# tesis_page5_adc_channels.net
KiCad netlist of a schematic drawn in Altium Designer
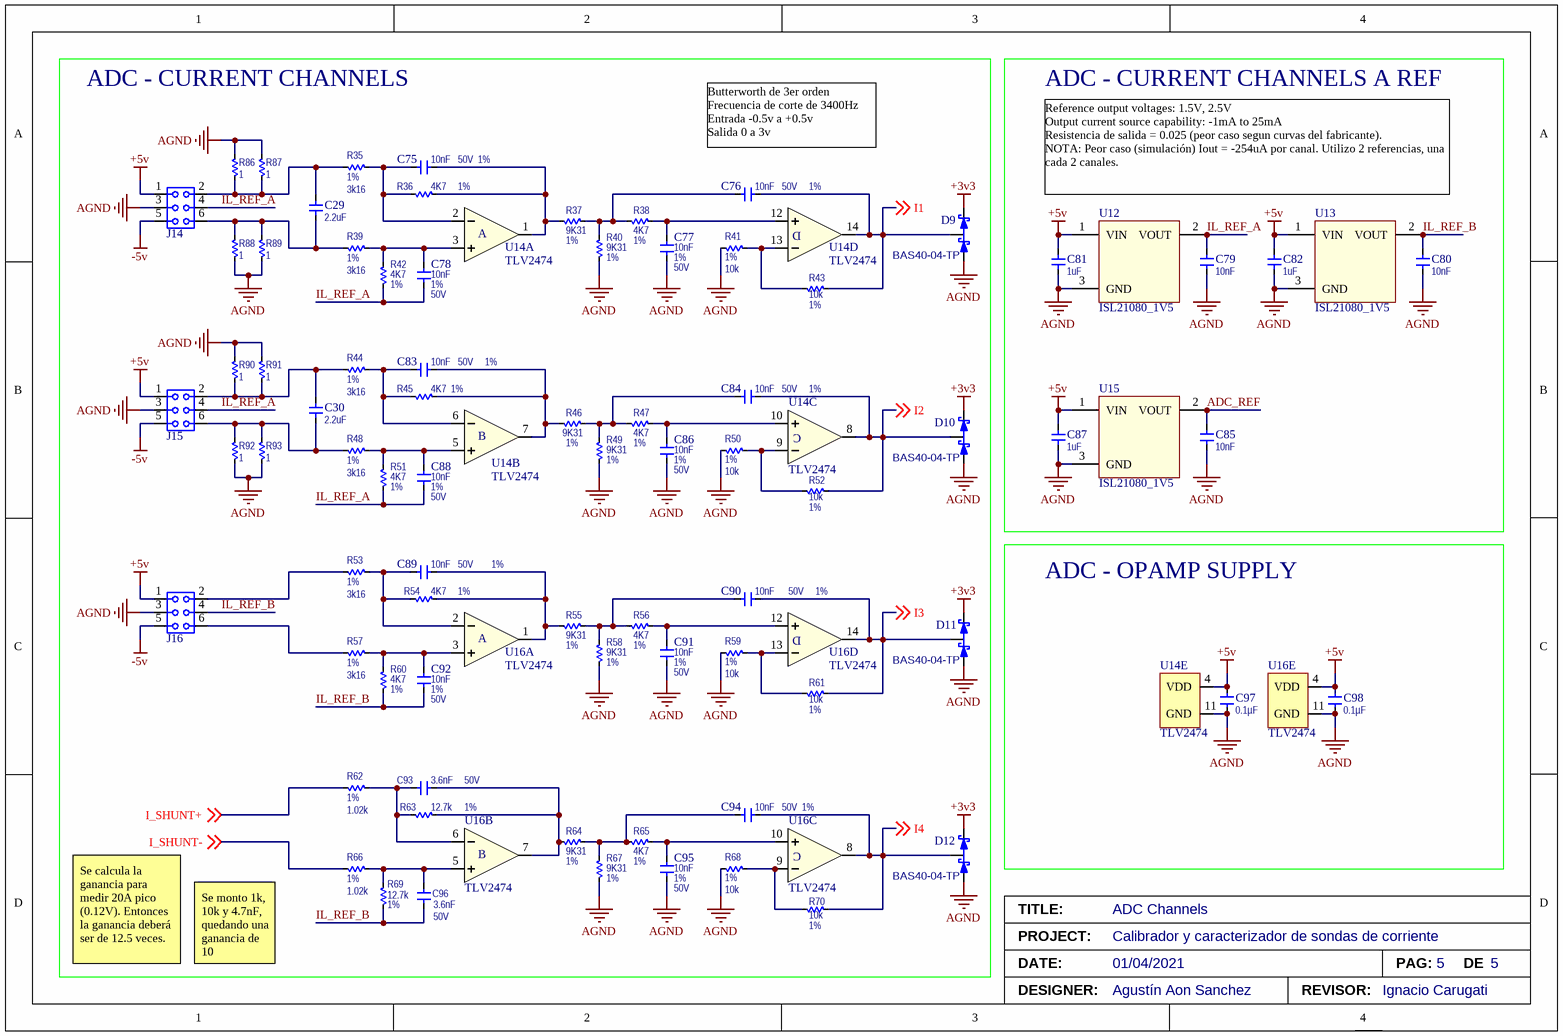
[diagram p0: tesis_page5_adc_channels.SchDoc]

(export (version "E")
  (design (tool "Eeschema 10.0.6"))
  (components
    (comp (ref "C29")
      (value "2.2uF")
      (footprint "CAPC3216X135N_B")
      (description "CAP CER 2.2UF 16V X7R 1206")
      (fields (field (name "MANUFACTURER") "YAGEO") (field (name "TOLERANCE") "10%"))
      (libsource (lib "lib_ic_CAP") (part "CAP_CC1206KKX7R7BB225_YAGEO"))
    )
    (comp (ref "C30")
      (value "2.2uF")
      (footprint "CAPC3216X135N_B")
      (description "CAP CER 2.2UF 16V X7R 1206")
      (fields (field (name "MANUFACTURER") "YAGEO") (field (name "TOLERANCE") "10%"))
      (libsource (lib "lib_ic_CAP") (part "CAP_CC1206KKX7R7BB225_YAGEO"))
    )
    (comp (ref "C75")
      (value "10nF")
      (footprint "CAPC2013X110N")
      (description "CAP CER 10000PF 50V NP0 0805")
      (fields
        (field (name "MANUFACTURER") "Murata Electronics North America")
        (field (name "TOLERANCE") "1%")
        (field (name "VOLTAGE RATING") "50V")
        (field (name "DIGIKEY PART NUMBER") "490-8295-1-ND")
      )
      (libsource (lib "pqm_v2_lib_cap") (part "CAP_GRM2195C1H103FA01D_MURATA"))
    )
    (comp (ref "C76")
      (value "10nF")
      (footprint "CAPC2013X110N")
      (description "CAP CER 10000PF 50V NP0 0805")
      (fields
        (field (name "MANUFACTURER") "Murata Electronics North America")
        (field (name "TOLERANCE") "1%")
        (field (name "VOLTAGE RATING") "50V")
        (field (name "DIGIKEY PART NUMBER") "490-8295-1-ND")
      )
      (libsource (lib "pqm_v2_lib_cap") (part "CAP_GRM2195C1H103FA01D_MURATA"))
    )
    (comp (ref "C77")
      (value "10nF")
      (footprint "CAPC2013X110N")
      (description "CAP CER 10000PF 50V NP0 0805")
      (fields
        (field (name "MANUFACTURER") "Murata Electronics North America")
        (field (name "TOLERANCE") "1%")
        (field (name "VOLTAGE RATING") "50V")
        (field (name "DIGIKEY PART NUMBER") "490-8295-1-ND")
      )
      (libsource (lib "pqm_v2_lib_cap") (part "CAP_GRM2195C1H103FA01D_MURATA"))
    )
    (comp (ref "C78")
      (value "10nF")
      (footprint "CAPC2013X110N")
      (description "CAP CER 10000PF 50V NP0 0805")
      (fields
        (field (name "MANUFACTURER") "Murata Electronics North America")
        (field (name "TOLERANCE") "1%")
        (field (name "VOLTAGE RATING") "50V")
        (field (name "DIGIKEY PART NUMBER") "490-8295-1-ND")
      )
      (libsource (lib "pqm_v2_lib_cap") (part "CAP_GRM2195C1H103FA01D_MURATA"))
    )
    (comp (ref "C79")
      (value "10nF")
      (footprint "CAPC2013X110N")
      (description "CAP CER 10000PF 50V NP0 0805")
      (fields
        (field (name "MANUFACTURER") "Murata Electronics North America")
        (field (name "DIGIKEY PART NUMBER") "490-8295-1-ND")
      )
      (libsource (lib "lib_ic_CAP") (part "CAP_GRM2195C1H103FA01D_MURATA"))
    )
    (comp (ref "C80")
      (value "10nF")
      (footprint "CAPC2013X110N")
      (description "CAP CER 10000PF 50V NP0 0805")
      (fields
        (field (name "MANUFACTURER") "Murata Electronics North America")
        (field (name "DIGIKEY PART NUMBER") "490-8295-1-ND")
      )
      (libsource (lib "lib_ic_CAP") (part "CAP_GRM2195C1H103FA01D_MURATA"))
    )
    (comp (ref "C81")
      (value "1uF")
      (footprint "CAPC2013X110N")
      (description "CAP CER 1UF 16V X7R 0805")
      (fields (field (name "MANUFACTURER") "YAGEO") (field (name "TOLERANCE") "10%"))
      (libsource (lib "pqm_v2_lib_cap") (part "CAP_CC0805KKX7R7BB105_YAGEO"))
    )
    (comp (ref "C82")
      (value "1uF")
      (footprint "CAPC2013X110N")
      (description "CAP CER 1UF 16V X7R 0805")
      (fields (field (name "MANUFACTURER") "YAGEO") (field (name "TOLERANCE") "10%"))
      (libsource (lib "pqm_v2_lib_cap") (part "CAP_CC0805KKX7R7BB105_YAGEO"))
    )
    (comp (ref "C83")
      (value "10nF")
      (footprint "CAPC2013X110N")
      (description "CAP CER 10000PF 50V NP0 0805")
      (fields
        (field (name "MANUFACTURER") "Murata Electronics North America")
        (field (name "TOLERANCE") "1%")
        (field (name "VOLTAGE RATING") "50V")
        (field (name "DIGIKEY PART NUMBER") "490-8295-1-ND")
      )
      (libsource (lib "pqm_v2_lib_cap") (part "CAP_GRM2195C1H103FA01D_MURATA"))
    )
    (comp (ref "C84")
      (value "10nF")
      (footprint "CAPC2013X110N")
      (description "CAP CER 10000PF 50V NP0 0805")
      (fields
        (field (name "MANUFACTURER") "Murata Electronics North America")
        (field (name "TOLERANCE") "1%")
        (field (name "VOLTAGE RATING") "50V")
        (field (name "DIGIKEY PART NUMBER") "490-8295-1-ND")
      )
      (libsource (lib "pqm_v2_lib_cap") (part "CAP_GRM2195C1H103FA01D_MURATA"))
    )
    (comp (ref "C85")
      (value "10nF")
      (footprint "CAPC2013X110N")
      (description "CAP CER 10000PF 50V NP0 0805")
      (fields
        (field (name "MANUFACTURER") "Murata Electronics North America")
        (field (name "DIGIKEY PART NUMBER") "490-8295-1-ND")
      )
      (libsource (lib "lib_ic_CAP") (part "CAP_GRM2195C1H103FA01D_MURATA"))
    )
    (comp (ref "C86")
      (value "10nF")
      (footprint "CAPC2013X110N")
      (description "CAP CER 10000PF 50V NP0 0805")
      (fields
        (field (name "MANUFACTURER") "Murata Electronics North America")
        (field (name "TOLERANCE") "1%")
        (field (name "VOLTAGE RATING") "50V")
        (field (name "DIGIKEY PART NUMBER") "490-8295-1-ND")
      )
      (libsource (lib "pqm_v2_lib_cap") (part "CAP_GRM2195C1H103FA01D_MURATA"))
    )
    (comp (ref "C87")
      (value "1uF")
      (footprint "CAPC2013X110N")
      (description "CAP CER 1UF 16V X7R 0805")
      (fields (field (name "MANUFACTURER") "YAGEO") (field (name "TOLERANCE") "10%"))
      (libsource (lib "pqm_v2_lib_cap") (part "CAP_CC0805KKX7R7BB105_YAGEO"))
    )
    (comp (ref "C88")
      (value "10nF")
      (footprint "CAPC2013X110N")
      (description "CAP CER 10000PF 50V NP0 0805")
      (fields
        (field (name "MANUFACTURER") "Murata Electronics North America")
        (field (name "TOLERANCE") "1%")
        (field (name "VOLTAGE RATING") "50V")
        (field (name "DIGIKEY PART NUMBER") "490-8295-1-ND")
      )
      (libsource (lib "pqm_v2_lib_cap") (part "CAP_GRM2195C1H103FA01D_MURATA"))
    )
    (comp (ref "C89")
      (value "10nF")
      (footprint "CAPC2013X110N")
      (description "CAP CER 10000PF 50V NP0 0805")
      (fields
        (field (name "MANUFACTURER") "Murata Electronics North America")
        (field (name "TOLERANCE") "1%")
        (field (name "VOLTAGE RATING") "50V")
        (field (name "DIGIKEY PART NUMBER") "490-8295-1-ND")
      )
      (libsource (lib "pqm_v2_lib_cap") (part "CAP_GRM2195C1H103FA01D_MURATA"))
    )
    (comp (ref "C90")
      (value "10nF")
      (footprint "CAPC2013X110N")
      (description "CAP CER 10000PF 50V NP0 0805")
      (fields
        (field (name "MANUFACTURER") "Murata Electronics North America")
        (field (name "TOLERANCE") "1%")
        (field (name "VOLTAGE RATING") "50V")
        (field (name "DIGIKEY PART NUMBER") "490-8295-1-ND")
      )
      (libsource (lib "pqm_v2_lib_cap") (part "CAP_GRM2195C1H103FA01D_MURATA"))
    )
    (comp (ref "C91")
      (value "10nF")
      (footprint "CAPC2013X110N")
      (description "CAP CER 10000PF 50V NP0 0805")
      (fields
        (field (name "MANUFACTURER") "Murata Electronics North America")
        (field (name "TOLERANCE") "1%")
        (field (name "VOLTAGE RATING") "50V")
        (field (name "DIGIKEY PART NUMBER") "490-8295-1-ND")
      )
      (libsource (lib "pqm_v2_lib_cap") (part "CAP_GRM2195C1H103FA01D_MURATA"))
    )
    (comp (ref "C92")
      (value "10nF")
      (footprint "CAPC2013X110N")
      (description "CAP CER 10000PF 50V NP0 0805")
      (fields
        (field (name "MANUFACTURER") "Murata Electronics North America")
        (field (name "TOLERANCE") "1%")
        (field (name "VOLTAGE RATING") "50V")
        (field (name "DIGIKEY PART NUMBER") "490-8295-1-ND")
      )
      (libsource (lib "pqm_v2_lib_cap") (part "CAP_GRM2195C1H103FA01D_MURATA"))
    )
    (comp (ref "C93")
      (value "3.6nF")
      (footprint "CAPC2013X110N")
      (description "CAP CER 3600PF 50V C0G/NP0 0805")
      (fields
        (field (name "MANUFACTURER") "Murata")
        (field (name "TOLERANCE") "5%")
        (field (name "VOLTAGE RATING") "50V")
      )
      (libsource (lib "lib_ic_CAP") (part "CAP_GRM2165C1H362JA01D"))
    )
    (comp (ref "C94")
      (value "10nF")
      (footprint "CAPC2013X110N")
      (description "CAP CER 10000PF 50V NP0 0805")
      (fields
        (field (name "MANUFACTURER") "Murata Electronics North America")
        (field (name "TOLERANCE") "1%")
        (field (name "VOLTAGE RATING") "50V")
        (field (name "DIGIKEY PART NUMBER") "490-8295-1-ND")
      )
      (libsource (lib "pqm_v2_lib_cap") (part "CAP_GRM2195C1H103FA01D_MURATA"))
    )
    (comp (ref "C95")
      (value "10nF")
      (footprint "CAPC2013X110N")
      (description "CAP CER 10000PF 50V NP0 0805")
      (fields
        (field (name "MANUFACTURER") "Murata Electronics North America")
        (field (name "TOLERANCE") "1%")
        (field (name "VOLTAGE RATING") "50V")
        (field (name "DIGIKEY PART NUMBER") "490-8295-1-ND")
      )
      (libsource (lib "pqm_v2_lib_cap") (part "CAP_GRM2195C1H103FA01D_MURATA"))
    )
    (comp (ref "C96")
      (value "3.6nF")
      (footprint "CAPC2013X110N")
      (description "CAP CER 3600PF 50V C0G/NP0 0805")
      (fields
        (field (name "MANUFACTURER") "Murata")
        (field (name "TOLERANCE") "5%")
        (field (name "VOLTAGE RATING") "50V")
      )
      (libsource (lib "lib_ic_CAP") (part "CAP_GRM2165C1H362JA01D"))
    )
    (comp (ref "C97")
      (value "0.1µF")
      (footprint "CAPC2013X110N")
      (description "CAP CER 0.1UF 25V 10% X7R 0805")
      (fields (field (name "MANUFACTURER") "Yageo") (field (name "TOLERANCE") "10%"))
      (libsource (lib "lib_ic_CAP") (part "CAP_CC0805KRX7R8BB104_YAGEO"))
    )
    (comp (ref "C98")
      (value "0.1µF")
      (footprint "CAPC2013X110N")
      (description "CAP CER 0.1UF 25V 10% X7R 0805")
      (fields (field (name "MANUFACTURER") "Yageo") (field (name "TOLERANCE") "10%"))
      (libsource (lib "lib_ic_CAP") (part "CAP_CC0805KRX7R8BB104_YAGEO"))
    )
    (comp (ref "D9")
      (value "BAS40-04-TP")
      (footprint "SOT23-3M")
      (description "DIODE ARRAY SCHOTTKY 40V SOT23")
      (fields (field (name "MANUFACTURER") "MCC"))
      (libsource (lib "lib_ic_DIO") (part "DIO_BAS40-04-TP"))
    )
    (comp (ref "D10")
      (value "BAS40-04-TP")
      (footprint "SOT23-3M")
      (description "DIODE ARRAY SCHOTTKY 40V SOT23")
      (fields (field (name "MANUFACTURER") "MCC"))
      (libsource (lib "lib_ic_DIO") (part "DIO_BAS40-04-TP"))
    )
    (comp (ref "D11")
      (value "BAS40-04-TP")
      (footprint "SOT23-3M")
      (description "DIODE ARRAY SCHOTTKY 40V SOT23")
      (fields (field (name "MANUFACTURER") "MCC"))
      (libsource (lib "lib_ic_DIO") (part "DIO_BAS40-04-TP"))
    )
    (comp (ref "D12")
      (value "BAS40-04-TP")
      (footprint "SOT23-3M")
      (description "DIODE ARRAY SCHOTTKY 40V SOT23")
      (fields (field (name "MANUFACTURER") "MCC"))
      (libsource (lib "lib_ic_DIO") (part "DIO_BAS40-04-TP"))
    )
    (comp (ref "J14")
      (value "CON_Header_2x3_90º")
      (footprint "HDR2X3-90º")
      (libsource (lib "lib_ic_CON") (part "CON_Header_2x3_90º"))
    )
    (comp (ref "J15")
      (value "CON_Header_2x3_90º")
      (footprint "HDR2X3-90º")
      (libsource (lib "lib_ic_CON") (part "CON_Header_2x3_90º"))
    )
    (comp (ref "J16")
      (value "CON_Header_2x3_90º")
      (footprint "HDR2X3-90º")
      (libsource (lib "lib_ic_CON") (part "CON_Header_2x3_90º"))
    )
    (comp (ref "R35")
      (value "3k16")
      (footprint "RESC2013X065BN")
      (description "RES SMD 3.16K OHM 1% 1/8W 0805")
      (fields
        (field (name "TOLERANCE") "1%")
        (field (name "MANUFACTURER") "Yageo")
        (field (name "DIGIKEY PART NUMBER") "311-3.16KCRCT-ND")
      )
      (libsource (lib "pqm_v2_lib_res") (part "RES_RC0805FR-073K16L_YAGEO"))
    )
    (comp (ref "R36")
      (value "4K7")
      (footprint "RESC2013X065BN")
      (description "RES SMD 4.7K OHM 1% 1/8W 0805")
      (fields
        (field (name "TOLERANCE") "1%")
        (field (name "MANUFACTURER") "Yageo")
        (field (name "DIGIKEY PART NUMBER") "311-4.70KCRCT-ND")
      )
      (libsource (lib "pqm_v2_lib_res") (part "RES_RC0805FR-074K7L_YAGEO"))
    )
    (comp (ref "R37")
      (value "9K31")
      (footprint "RESC2013X065BN")
      (description "RES SMD 9.31K OHM 1% 1/8W 0805")
      (fields
        (field (name "TOLERANCE") "1%")
        (field (name "MANUFACTURER") "Yageo")
        (field (name "DIGIKEY PART NUMBER") "311-9.31KCRCT-ND")
      )
      (libsource (lib "pqm_v2_lib_res") (part "RES_RC0805FR-079K31L_YAGEO"))
    )
    (comp (ref "R38")
      (value "4K7")
      (footprint "RESC2013X065BN")
      (description "RES SMD 4.7K OHM 1% 1/8W 0805")
      (fields
        (field (name "TOLERANCE") "1%")
        (field (name "MANUFACTURER") "Yageo")
        (field (name "DIGIKEY PART NUMBER") "311-4.70KCRCT-ND")
      )
      (libsource (lib "pqm_v2_lib_res") (part "RES_RC0805FR-074K7L_YAGEO"))
    )
    (comp (ref "R39")
      (value "3k16")
      (footprint "RESC2013X065BN")
      (description "RES SMD 3.16K OHM 1% 1/8W 0805")
      (fields
        (field (name "TOLERANCE") "1%")
        (field (name "MANUFACTURER") "Yageo")
        (field (name "DIGIKEY PART NUMBER") "311-3.16KCRCT-ND")
      )
      (libsource (lib "pqm_v2_lib_res") (part "RES_RC0805FR-073K16L_YAGEO"))
    )
    (comp (ref "R40")
      (value "9K31")
      (footprint "RESC2013X065BN")
      (description "RES SMD 9.31K OHM 1% 1/8W 0805")
      (fields
        (field (name "TOLERANCE") "1%")
        (field (name "MANUFACTURER") "Yageo")
        (field (name "DIGIKEY PART NUMBER") "311-9.31KCRCT-ND")
      )
      (libsource (lib "pqm_v2_lib_res") (part "RES_RC0805FR-079K31L_YAGEO"))
    )
    (comp (ref "R41")
      (value "10k")
      (footprint "RESC2013X065BN")
      (description "RES SMD 10K OHM 1% 1/8W 0805")
      (fields
        (field (name "TOLERANCE") "1%")
        (field (name "MANUFACTURER") "Yageo")
        (field (name "DIGIKEY PART NUMBER") "311-10.0KCRCT-ND")
      )
      (libsource (lib "pqm_v2_lib_res") (part "RES_RC0805FR-0710KL_YAGEO"))
    )
    (comp (ref "R42")
      (value "4K7")
      (footprint "RESC2013X065BN")
      (description "RES SMD 4.7K OHM 1% 1/8W 0805")
      (fields
        (field (name "TOLERANCE") "1%")
        (field (name "MANUFACTURER") "Yageo")
        (field (name "DIGIKEY PART NUMBER") "311-4.70KCRCT-ND")
      )
      (libsource (lib "pqm_v2_lib_res") (part "RES_RC0805FR-074K7L_YAGEO"))
    )
    (comp (ref "R43")
      (value "10k")
      (footprint "RESC2013X065BN")
      (description "RES SMD 10K OHM 1% 1/8W 0805")
      (fields
        (field (name "TOLERANCE") "1%")
        (field (name "MANUFACTURER") "Yageo")
        (field (name "DIGIKEY PART NUMBER") "311-10.0KCRCT-ND")
      )
      (libsource (lib "pqm_v2_lib_res") (part "RES_RC0805FR-0710KL_YAGEO"))
    )
    (comp (ref "R44")
      (value "3k16")
      (footprint "RESC2013X065BN")
      (description "RES SMD 3.16K OHM 1% 1/8W 0805")
      (fields
        (field (name "TOLERANCE") "1%")
        (field (name "MANUFACTURER") "Yageo")
        (field (name "DIGIKEY PART NUMBER") "311-3.16KCRCT-ND")
      )
      (libsource (lib "pqm_v2_lib_res") (part "RES_RC0805FR-073K16L_YAGEO"))
    )
    (comp (ref "R45")
      (value "4K7")
      (footprint "RESC2013X065BN")
      (description "RES SMD 4.7K OHM 1% 1/8W 0805")
      (fields
        (field (name "TOLERANCE") "1%")
        (field (name "MANUFACTURER") "Yageo")
        (field (name "DIGIKEY PART NUMBER") "311-4.70KCRCT-ND")
      )
      (libsource (lib "pqm_v2_lib_res") (part "RES_RC0805FR-074K7L_YAGEO"))
    )
    (comp (ref "R46")
      (value "9K31")
      (footprint "RESC2013X065BN")
      (description "RES SMD 9.31K OHM 1% 1/8W 0805")
      (fields
        (field (name "TOLERANCE") "1%")
        (field (name "MANUFACTURER") "Yageo")
        (field (name "DIGIKEY PART NUMBER") "311-9.31KCRCT-ND")
      )
      (libsource (lib "pqm_v2_lib_res") (part "RES_RC0805FR-079K31L_YAGEO"))
    )
    (comp (ref "R47")
      (value "4K7")
      (footprint "RESC2013X065BN")
      (description "RES SMD 4.7K OHM 1% 1/8W 0805")
      (fields
        (field (name "TOLERANCE") "1%")
        (field (name "MANUFACTURER") "Yageo")
        (field (name "DIGIKEY PART NUMBER") "311-4.70KCRCT-ND")
      )
      (libsource (lib "pqm_v2_lib_res") (part "RES_RC0805FR-074K7L_YAGEO"))
    )
    (comp (ref "R48")
      (value "3k16")
      (footprint "RESC2013X065BN")
      (description "RES SMD 3.16K OHM 1% 1/8W 0805")
      (fields
        (field (name "TOLERANCE") "1%")
        (field (name "MANUFACTURER") "Yageo")
        (field (name "DIGIKEY PART NUMBER") "311-3.16KCRCT-ND")
      )
      (libsource (lib "pqm_v2_lib_res") (part "RES_RC0805FR-073K16L_YAGEO"))
    )
    (comp (ref "R49")
      (value "9K31")
      (footprint "RESC2013X065BN")
      (description "RES SMD 9.31K OHM 1% 1/8W 0805")
      (fields
        (field (name "TOLERANCE") "1%")
        (field (name "MANUFACTURER") "Yageo")
        (field (name "DIGIKEY PART NUMBER") "311-9.31KCRCT-ND")
      )
      (libsource (lib "pqm_v2_lib_res") (part "RES_RC0805FR-079K31L_YAGEO"))
    )
    (comp (ref "R50")
      (value "10k")
      (footprint "RESC2013X065BN")
      (description "RES SMD 10K OHM 1% 1/8W 0805")
      (fields
        (field (name "TOLERANCE") "1%")
        (field (name "MANUFACTURER") "Yageo")
        (field (name "DIGIKEY PART NUMBER") "311-10.0KCRCT-ND")
      )
      (libsource (lib "pqm_v2_lib_res") (part "RES_RC0805FR-0710KL_YAGEO"))
    )
    (comp (ref "R51")
      (value "4K7")
      (footprint "RESC2013X065BN")
      (description "RES SMD 4.7K OHM 1% 1/8W 0805")
      (fields
        (field (name "TOLERANCE") "1%")
        (field (name "MANUFACTURER") "Yageo")
        (field (name "DIGIKEY PART NUMBER") "311-4.70KCRCT-ND")
      )
      (libsource (lib "pqm_v2_lib_res") (part "RES_RC0805FR-074K7L_YAGEO"))
    )
    (comp (ref "R52")
      (value "10k")
      (footprint "RESC2013X065BN")
      (description "RES SMD 10K OHM 1% 1/8W 0805")
      (fields
        (field (name "TOLERANCE") "1%")
        (field (name "MANUFACTURER") "Yageo")
        (field (name "DIGIKEY PART NUMBER") "311-10.0KCRCT-ND")
      )
      (libsource (lib "pqm_v2_lib_res") (part "RES_RC0805FR-0710KL_YAGEO"))
    )
    (comp (ref "R53")
      (value "3k16")
      (footprint "RESC2013X065BN")
      (description "RES SMD 3.16K OHM 1% 1/8W 0805")
      (fields
        (field (name "TOLERANCE") "1%")
        (field (name "MANUFACTURER") "Yageo")
        (field (name "DIGIKEY PART NUMBER") "311-3.16KCRCT-ND")
      )
      (libsource (lib "pqm_v2_lib_res") (part "RES_RC0805FR-073K16L_YAGEO"))
    )
    (comp (ref "R54")
      (value "4K7")
      (footprint "RESC2013X065BN")
      (description "RES SMD 4.7K OHM 1% 1/8W 0805")
      (fields
        (field (name "TOLERANCE") "1%")
        (field (name "MANUFACTURER") "Yageo")
        (field (name "DIGIKEY PART NUMBER") "311-4.70KCRCT-ND")
      )
      (libsource (lib "pqm_v2_lib_res") (part "RES_RC0805FR-074K7L_YAGEO"))
    )
    (comp (ref "R55")
      (value "9K31")
      (footprint "RESC2013X065BN")
      (description "RES SMD 9.31K OHM 1% 1/8W 0805")
      (fields
        (field (name "TOLERANCE") "1%")
        (field (name "MANUFACTURER") "Yageo")
        (field (name "DIGIKEY PART NUMBER") "311-9.31KCRCT-ND")
      )
      (libsource (lib "pqm_v2_lib_res") (part "RES_RC0805FR-079K31L_YAGEO"))
    )
    (comp (ref "R56")
      (value "4K7")
      (footprint "RESC2013X065BN")
      (description "RES SMD 4.7K OHM 1% 1/8W 0805")
      (fields
        (field (name "TOLERANCE") "1%")
        (field (name "MANUFACTURER") "Yageo")
        (field (name "DIGIKEY PART NUMBER") "311-4.70KCRCT-ND")
      )
      (libsource (lib "pqm_v2_lib_res") (part "RES_RC0805FR-074K7L_YAGEO"))
    )
    (comp (ref "R57")
      (value "3k16")
      (footprint "RESC2013X065BN")
      (description "RES SMD 3.16K OHM 1% 1/8W 0805")
      (fields
        (field (name "TOLERANCE") "1%")
        (field (name "MANUFACTURER") "Yageo")
        (field (name "DIGIKEY PART NUMBER") "311-3.16KCRCT-ND")
      )
      (libsource (lib "pqm_v2_lib_res") (part "RES_RC0805FR-073K16L_YAGEO"))
    )
    (comp (ref "R58")
      (value "9K31")
      (footprint "RESC2013X065BN")
      (description "RES SMD 9.31K OHM 1% 1/8W 0805")
      (fields
        (field (name "TOLERANCE") "1%")
        (field (name "MANUFACTURER") "Yageo")
        (field (name "DIGIKEY PART NUMBER") "311-9.31KCRCT-ND")
      )
      (libsource (lib "pqm_v2_lib_res") (part "RES_RC0805FR-079K31L_YAGEO"))
    )
    (comp (ref "R59")
      (value "10k")
      (footprint "RESC2013X065BN")
      (description "RES SMD 10K OHM 1% 1/8W 0805")
      (fields
        (field (name "TOLERANCE") "1%")
        (field (name "MANUFACTURER") "Yageo")
        (field (name "DIGIKEY PART NUMBER") "311-10.0KCRCT-ND")
      )
      (libsource (lib "pqm_v2_lib_res") (part "RES_RC0805FR-0710KL_YAGEO"))
    )
    (comp (ref "R60")
      (value "4K7")
      (footprint "RESC2013X065BN")
      (description "RES SMD 4.7K OHM 1% 1/8W 0805")
      (fields
        (field (name "TOLERANCE") "1%")
        (field (name "MANUFACTURER") "Yageo")
        (field (name "DIGIKEY PART NUMBER") "311-4.70KCRCT-ND")
      )
      (libsource (lib "pqm_v2_lib_res") (part "RES_RC0805FR-074K7L_YAGEO"))
    )
    (comp (ref "R61")
      (value "10k")
      (footprint "RESC2013X065BN")
      (description "RES SMD 10K OHM 1% 1/8W 0805")
      (fields
        (field (name "TOLERANCE") "1%")
        (field (name "MANUFACTURER") "Yageo")
        (field (name "DIGIKEY PART NUMBER") "311-10.0KCRCT-ND")
      )
      (libsource (lib "pqm_v2_lib_res") (part "RES_RC0805FR-0710KL_YAGEO"))
    )
    (comp (ref "R62")
      (value "1.02k")
      (footprint "RESC2013X065BN")
      (description "RES SMD 1.02K OHM 1% 1/8W 0805")
      (fields
        (field (name "TOLERANCE") "1%")
        (field (name "MANUFACTURER") "Yageo")
        (field (name "MANUFACTURER PART NUMBER") "RC0805FR-071K02L")
      )
      (libsource (lib "lib_ic_RES") (part "RES_RC0805FR-071K02L"))
    )
    (comp (ref "R63")
      (value "12.7k")
      (footprint "RESC2013X065BN")
      (description "RES SMD 12.7K OHM 1% 1/8W 0805")
      (fields
        (field (name "TOLERANCE") "1%")
        (field (name "MANUFACTURER") "Yageo")
        (field (name "MANUFACTURER PART NUMBER") "RC0805FR-0712K7L")
      )
      (libsource (lib "lib_ic_RES") (part "RES_RC0805FR-0712K7L"))
    )
    (comp (ref "R64")
      (value "9K31")
      (footprint "RESC2013X065BN")
      (description "RES SMD 9.31K OHM 1% 1/8W 0805")
      (fields
        (field (name "TOLERANCE") "1%")
        (field (name "MANUFACTURER") "Yageo")
        (field (name "DIGIKEY PART NUMBER") "311-9.31KCRCT-ND")
      )
      (libsource (lib "pqm_v2_lib_res") (part "RES_RC0805FR-079K31L_YAGEO"))
    )
    (comp (ref "R65")
      (value "4K7")
      (footprint "RESC2013X065BN")
      (description "RES SMD 4.7K OHM 1% 1/8W 0805")
      (fields
        (field (name "TOLERANCE") "1%")
        (field (name "MANUFACTURER") "Yageo")
        (field (name "DIGIKEY PART NUMBER") "311-4.70KCRCT-ND")
      )
      (libsource (lib "pqm_v2_lib_res") (part "RES_RC0805FR-074K7L_YAGEO"))
    )
    (comp (ref "R66")
      (value "1.02k")
      (footprint "RESC2013X065BN")
      (description "RES SMD 1.02K OHM 1% 1/8W 0805")
      (fields
        (field (name "TOLERANCE") "1%")
        (field (name "MANUFACTURER") "Yageo")
        (field (name "MANUFACTURER PART NUMBER") "RC0805FR-071K02L")
      )
      (libsource (lib "lib_ic_RES") (part "RES_RC0805FR-071K02L"))
    )
    (comp (ref "R67")
      (value "9K31")
      (footprint "RESC2013X065BN")
      (description "RES SMD 9.31K OHM 1% 1/8W 0805")
      (fields
        (field (name "TOLERANCE") "1%")
        (field (name "MANUFACTURER") "Yageo")
        (field (name "DIGIKEY PART NUMBER") "311-9.31KCRCT-ND")
      )
      (libsource (lib "pqm_v2_lib_res") (part "RES_RC0805FR-079K31L_YAGEO"))
    )
    (comp (ref "R68")
      (value "10k")
      (footprint "RESC2013X065BN")
      (description "RES SMD 10K OHM 1% 1/8W 0805")
      (fields
        (field (name "TOLERANCE") "1%")
        (field (name "MANUFACTURER") "Yageo")
        (field (name "DIGIKEY PART NUMBER") "311-10.0KCRCT-ND")
      )
      (libsource (lib "pqm_v2_lib_res") (part "RES_RC0805FR-0710KL_YAGEO"))
    )
    (comp (ref "R69")
      (value "12.7k")
      (footprint "RESC2013X065BN")
      (description "RES SMD 12.7K OHM 1% 1/8W 0805")
      (fields
        (field (name "TOLERANCE") "1%")
        (field (name "MANUFACTURER") "Yageo")
        (field (name "MANUFACTURER PART NUMBER") "RC0805FR-0712K7L")
      )
      (libsource (lib "lib_ic_RES") (part "RES_RC0805FR-0712K7L"))
    )
    (comp (ref "R70")
      (value "10k")
      (footprint "RESC2013X065BN")
      (description "RES SMD 10K OHM 1% 1/8W 0805")
      (fields
        (field (name "TOLERANCE") "1%")
        (field (name "MANUFACTURER") "Yageo")
        (field (name "DIGIKEY PART NUMBER") "311-10.0KCRCT-ND")
      )
      (libsource (lib "pqm_v2_lib_res") (part "RES_RC0805FR-0710KL_YAGEO"))
    )
    (comp (ref "R86")
      (value "1")
      (footprint "RESC3216N")
      (description "YAGEO - RC1206FR-071RL - RES, THICK FILM, 1R, 1%, 0.25W, 1206")
      (fields (field (name "TOLERANCE") "1%") (field (name "MANUFACTURER") "Yageo"))
      (libsource (lib "lib_ic_RES") (part "RES_RC1206FR-071RL"))
    )
    (comp (ref "R87")
      (value "1")
      (footprint "RESC3216N")
      (description "YAGEO - RC1206FR-071RL - RES, THICK FILM, 1R, 1%, 0.25W, 1206")
      (fields (field (name "TOLERANCE") "1%") (field (name "MANUFACTURER") "Yageo"))
      (libsource (lib "lib_ic_RES") (part "RES_RC1206FR-071RL"))
    )
    (comp (ref "R88")
      (value "1")
      (footprint "RESC3216N")
      (description "YAGEO - RC1206FR-071RL - RES, THICK FILM, 1R, 1%, 0.25W, 1206")
      (fields (field (name "TOLERANCE") "1%") (field (name "MANUFACTURER") "Yageo"))
      (libsource (lib "lib_ic_RES") (part "RES_RC1206FR-071RL"))
    )
    (comp (ref "R89")
      (value "1")
      (footprint "RESC3216N")
      (description "YAGEO - RC1206FR-071RL - RES, THICK FILM, 1R, 1%, 0.25W, 1206")
      (fields (field (name "TOLERANCE") "1%") (field (name "MANUFACTURER") "Yageo"))
      (libsource (lib "lib_ic_RES") (part "RES_RC1206FR-071RL"))
    )
    (comp (ref "R90")
      (value "1")
      (footprint "RESC3216N")
      (description "YAGEO - RC1206FR-071RL - RES, THICK FILM, 1R, 1%, 0.25W, 1206")
      (fields (field (name "TOLERANCE") "1%") (field (name "MANUFACTURER") "Yageo"))
      (libsource (lib "lib_ic_RES") (part "RES_RC1206FR-071RL"))
    )
    (comp (ref "R91")
      (value "1")
      (footprint "RESC3216N")
      (description "YAGEO - RC1206FR-071RL - RES, THICK FILM, 1R, 1%, 0.25W, 1206")
      (fields (field (name "TOLERANCE") "1%") (field (name "MANUFACTURER") "Yageo"))
      (libsource (lib "lib_ic_RES") (part "RES_RC1206FR-071RL"))
    )
    (comp (ref "R92")
      (value "1")
      (footprint "RESC3216N")
      (description "YAGEO - RC1206FR-071RL - RES, THICK FILM, 1R, 1%, 0.25W, 1206")
      (fields (field (name "TOLERANCE") "1%") (field (name "MANUFACTURER") "Yageo"))
      (libsource (lib "lib_ic_RES") (part "RES_RC1206FR-071RL"))
    )
    (comp (ref "R93")
      (value "1")
      (footprint "RESC3216N")
      (description "YAGEO - RC1206FR-071RL - RES, THICK FILM, 1R, 1%, 0.25W, 1206")
      (fields (field (name "TOLERANCE") "1%") (field (name "MANUFACTURER") "Yageo"))
      (libsource (lib "lib_ic_RES") (part "RES_RC1206FR-071RL"))
    )
    (comp (ref "U12")
      (value "ISL21080_1V5")
      (footprint "SOT23-3M")
      (description "IC VREF SERIES 1.5V SOT23-3")
      (fields
        (field (name "DIGIKEY PART NUMBER") "ISL21080CIH315Z-TKCT-ND")
        (field (name "MOUSER PART NUMBER") "968-ISL21080CIH315ZT")
      )
      (libsource (lib "lib_ic_IC") (part "IC_ISL21080CIH315Z-TK_INTERSIL"))
    )
    (comp (ref "U13")
      (value "ISL21080_1V5")
      (footprint "SOT23-3M")
      (description "IC VREF SERIES 1.5V SOT23-3")
      (fields
        (field (name "DIGIKEY PART NUMBER") "ISL21080CIH315Z-TKCT-ND")
        (field (name "MOUSER PART NUMBER") "968-ISL21080CIH315ZT")
      )
      (libsource (lib "lib_ic_IC") (part "IC_ISL21080CIH315Z-TK_INTERSIL"))
    )
    (comp (ref "U14")
      (value "TLV2474")
      (footprint "SOIC127P600-14AN")
      (description "IC OPAMP GP 2.8MHZ RRO 14SOIC")
      (fields
        (field (name "MANUFACTURER") "Texas Instrument")
        (field (name "DIGIKEY PART NUMBER") "296-2442-1-ND")
      )
      (libsource (lib "pqm_v2_lib_ic") (part "IC_TLV2474_ANALOG"))
    )
    (comp (ref "U15")
      (value "ISL21080_1V5")
      (footprint "SOT23-3M")
      (description "IC VREF SERIES 1.5V SOT23-3")
      (fields
        (field (name "DIGIKEY PART NUMBER") "ISL21080CIH315Z-TKCT-ND")
        (field (name "MOUSER PART NUMBER") "968-ISL21080CIH315ZT")
      )
      (libsource (lib "lib_ic_IC") (part "IC_ISL21080CIH315Z-TK_INTERSIL"))
    )
    (comp (ref "U16")
      (value "TLV2474")
      (footprint "SOIC127P600-14AN")
      (description "IC OPAMP GP 2.8MHZ RRO 14SOIC")
      (fields
        (field (name "MANUFACTURER") "Texas Instrument")
        (field (name "DIGIKEY PART NUMBER") "296-2442-1-ND")
      )
      (libsource (lib "pqm_v2_lib_ic") (part "IC_TLV2474_ANALOG"))
    )
  )
  (nets
    (net (code "1") (name "+3v3") (class "Default")
      (node (ref "D10") (pin "2") (pinfunction "2_2") (pintype "passive"))
      (node (ref "D11") (pin "2") (pinfunction "2_2") (pintype "passive"))
      (node (ref "D12") (pin "2") (pinfunction "2_2") (pintype "passive"))
      (node (ref "D9") (pin "2") (pinfunction "2_2") (pintype "passive"))
    )
    (net (code "2") (name "+5v") (class "Default")
      (node (ref "C81") (pin "1") (pinfunction "T1_1") (pintype "passive"))
      (node (ref "C82") (pin "1") (pinfunction "T1_1") (pintype "passive"))
      (node (ref "C87") (pin "1") (pinfunction "T1_1") (pintype "passive"))
      (node (ref "C97") (pin "1") (pinfunction "T1_1") (pintype "passive"))
      (node (ref "C98") (pin "1") (pinfunction "T1_1") (pintype "passive"))
      (node (ref "J14") (pin "1") (pinfunction "1_1") (pintype "passive"))
      (node (ref "J15") (pin "1") (pinfunction "1_1") (pintype "passive"))
      (node (ref "J16") (pin "1") (pinfunction "1_1") (pintype "passive"))
      (node (ref "U12") (pin "1") (pinfunction "VIN_1") (pintype "passive"))
      (node (ref "U13") (pin "1") (pinfunction "VIN_1") (pintype "passive"))
      (node (ref "U14") (pin "4") (pinfunction "VDD_4") (pintype "passive"))
      (node (ref "U15") (pin "1") (pinfunction "VIN_1") (pintype "passive"))
      (node (ref "U16") (pin "4") (pinfunction "VDD_4") (pintype "passive"))
    )
    (net (code "3") (name "-5v") (class "Default")
      (node (ref "J14") (pin "5") (pinfunction "5_5") (pintype "passive"))
      (node (ref "J15") (pin "5") (pinfunction "5_5") (pintype "passive"))
      (node (ref "J16") (pin "5") (pinfunction "5_5") (pintype "passive"))
    )
    (net (code "4") (name "/ADC_REF") (class "Default")
      (node (ref "C85") (pin "1") (pinfunction "T1_1") (pintype "passive"))
      (node (ref "U15") (pin "2") (pinfunction "VOUT_2") (pintype "passive"))
    )
    (net (code "5") (name "/IL_REF_A") (class "Default")
      (node (ref "C78") (pin "1") (pinfunction "T1_1") (pintype "passive"))
      (node (ref "C79") (pin "1") (pinfunction "T1_1") (pintype "passive"))
      (node (ref "C88") (pin "1") (pinfunction "T1_1") (pintype "passive"))
      (node (ref "J14") (pin "4") (pinfunction "4_4") (pintype "passive"))
      (node (ref "J15") (pin "4") (pinfunction "4_4") (pintype "passive"))
      (node (ref "R42") (pin "2") (pinfunction "T2_2") (pintype "passive"))
      (node (ref "R51") (pin "2") (pinfunction "T2_2") (pintype "passive"))
      (node (ref "U12") (pin "2") (pinfunction "VOUT_2") (pintype "passive"))
    )
    (net (code "6") (name "/IL_REF_B") (class "Default")
      (node (ref "C80") (pin "1") (pinfunction "T1_1") (pintype "passive"))
      (node (ref "C92") (pin "1") (pinfunction "T1_1") (pintype "passive"))
      (node (ref "C96") (pin "1") (pinfunction "T1_1") (pintype "passive"))
      (node (ref "J16") (pin "4") (pinfunction "4_4") (pintype "passive"))
      (node (ref "R60") (pin "2") (pinfunction "T2_2") (pintype "passive"))
      (node (ref "R69") (pin "2") (pinfunction "T2_2") (pintype "passive"))
      (node (ref "U13") (pin "2") (pinfunction "VOUT_2") (pintype "passive"))
    )
    (net (code "7") (name "AGND") (class "Default")
      (node (ref "C77") (pin "1") (pinfunction "T1_1") (pintype "passive"))
      (node (ref "C79") (pin "2") (pinfunction "T2_2") (pintype "passive"))
      (node (ref "C80") (pin "2") (pinfunction "T2_2") (pintype "passive"))
      (node (ref "C81") (pin "2") (pinfunction "T2_2") (pintype "passive"))
      (node (ref "C82") (pin "2") (pinfunction "T2_2") (pintype "passive"))
      (node (ref "C85") (pin "2") (pinfunction "T2_2") (pintype "passive"))
      (node (ref "C86") (pin "1") (pinfunction "T1_1") (pintype "passive"))
      (node (ref "C87") (pin "2") (pinfunction "T2_2") (pintype "passive"))
      (node (ref "C91") (pin "1") (pinfunction "T1_1") (pintype "passive"))
      (node (ref "C95") (pin "1") (pinfunction "T1_1") (pintype "passive"))
      (node (ref "C97") (pin "2") (pinfunction "T2_2") (pintype "passive"))
      (node (ref "C98") (pin "2") (pinfunction "T2_2") (pintype "passive"))
      (node (ref "D10") (pin "1") (pinfunction "1_1") (pintype "passive"))
      (node (ref "D11") (pin "1") (pinfunction "1_1") (pintype "passive"))
      (node (ref "D12") (pin "1") (pinfunction "1_1") (pintype "passive"))
      (node (ref "D9") (pin "1") (pinfunction "1_1") (pintype "passive"))
      (node (ref "J14") (pin "3") (pinfunction "3_3") (pintype "passive"))
      (node (ref "J15") (pin "3") (pinfunction "3_3") (pintype "passive"))
      (node (ref "J16") (pin "3") (pinfunction "3_3") (pintype "passive"))
      (node (ref "R40") (pin "1") (pinfunction "T1_1") (pintype "passive"))
      (node (ref "R41") (pin "1") (pinfunction "T1_1") (pintype "passive"))
      (node (ref "R49") (pin "1") (pinfunction "T1_1") (pintype "passive"))
      (node (ref "R50") (pin "1") (pinfunction "T1_1") (pintype "passive"))
      (node (ref "R58") (pin "1") (pinfunction "T1_1") (pintype "passive"))
      (node (ref "R59") (pin "1") (pinfunction "T1_1") (pintype "passive"))
      (node (ref "R67") (pin "1") (pinfunction "T1_1") (pintype "passive"))
      (node (ref "R68") (pin "1") (pinfunction "T1_1") (pintype "passive"))
      (node (ref "R86") (pin "2") (pinfunction "T2_2") (pintype "passive"))
      (node (ref "R87") (pin "2") (pinfunction "T2_2") (pintype "passive"))
      (node (ref "R88") (pin "1") (pinfunction "T1_1") (pintype "passive"))
      (node (ref "R89") (pin "1") (pinfunction "T1_1") (pintype "passive"))
      (node (ref "R90") (pin "2") (pinfunction "T2_2") (pintype "passive"))
      (node (ref "R91") (pin "2") (pinfunction "T2_2") (pintype "passive"))
      (node (ref "R92") (pin "1") (pinfunction "T1_1") (pintype "passive"))
      (node (ref "R93") (pin "1") (pinfunction "T1_1") (pintype "passive"))
      (node (ref "U12") (pin "3") (pinfunction "GND_3") (pintype "passive"))
      (node (ref "U13") (pin "3") (pinfunction "GND_3") (pintype "passive"))
      (node (ref "U14") (pin "11") (pinfunction "GND_11") (pintype "passive"))
      (node (ref "U15") (pin "3") (pinfunction "GND_3") (pintype "passive"))
      (node (ref "U16") (pin "11") (pinfunction "GND_11") (pintype "passive"))
    )
    (net (code "8") (name "I1") (class "Default")
      (node (ref "C76") (pin "2") (pinfunction "T2_2") (pintype "passive"))
      (node (ref "D9") (pin "3") (pinfunction "3_3") (pintype "passive"))
      (node (ref "R43") (pin "1") (pinfunction "T1_1") (pintype "passive"))
      (node (ref "U14") (pin "14") (pinfunction "OUTD_14") (pintype "passive"))
    )
    (net (code "9") (name "I2") (class "Default")
      (node (ref "C84") (pin "2") (pinfunction "T2_2") (pintype "passive"))
      (node (ref "D10") (pin "3") (pinfunction "3_3") (pintype "passive"))
      (node (ref "R52") (pin "1") (pinfunction "T1_1") (pintype "passive"))
      (node (ref "U14") (pin "8") (pinfunction "OUTC_8") (pintype "passive"))
    )
    (net (code "10") (name "I3") (class "Default")
      (node (ref "C90") (pin "2") (pinfunction "T2_2") (pintype "passive"))
      (node (ref "D11") (pin "3") (pinfunction "3_3") (pintype "passive"))
      (node (ref "R61") (pin "1") (pinfunction "T1_1") (pintype "passive"))
      (node (ref "U16") (pin "14") (pinfunction "OUTD_14") (pintype "passive"))
    )
    (net (code "11") (name "I4") (class "Default")
      (node (ref "C94") (pin "2") (pinfunction "T2_2") (pintype "passive"))
      (node (ref "D12") (pin "3") (pinfunction "3_3") (pintype "passive"))
      (node (ref "R70") (pin "1") (pinfunction "T1_1") (pintype "passive"))
      (node (ref "U16") (pin "8") (pinfunction "OUTC_8") (pintype "passive"))
    )
    (net (code "12") (name "I_SHUNT+") (class "Default")
      (node (ref "R62") (pin "2") (pinfunction "T2_2") (pintype "passive"))
    )
    (net (code "13") (name "I_SHUNT-") (class "Default")
      (node (ref "R66") (pin "2") (pinfunction "T2_2") (pintype "passive"))
    )
    (net (code "14") (name "Net-(C29-T1)") (class "Default")
      (node (ref "C29") (pin "1") (pinfunction "T1_1") (pintype "passive"))
      (node (ref "J14") (pin "2") (pinfunction "2_2") (pintype "passive"))
      (node (ref "R35") (pin "2") (pinfunction "T2_2") (pintype "passive"))
      (node (ref "R86") (pin "1") (pinfunction "T1_1") (pintype "passive"))
      (node (ref "R87") (pin "1") (pinfunction "T1_1") (pintype "passive"))
    )
    (net (code "15") (name "Net-(C29-T2)") (class "Default")
      (node (ref "C29") (pin "2") (pinfunction "T2_2") (pintype "passive"))
      (node (ref "J14") (pin "6") (pinfunction "6_6") (pintype "passive"))
      (node (ref "R39") (pin "2") (pinfunction "T2_2") (pintype "passive"))
      (node (ref "R88") (pin "2") (pinfunction "T2_2") (pintype "passive"))
      (node (ref "R89") (pin "2") (pinfunction "T2_2") (pintype "passive"))
    )
    (net (code "16") (name "Net-(C30-T1)") (class "Default")
      (node (ref "C30") (pin "1") (pinfunction "T1_1") (pintype "passive"))
      (node (ref "J15") (pin "2") (pinfunction "2_2") (pintype "passive"))
      (node (ref "R44") (pin "2") (pinfunction "T2_2") (pintype "passive"))
      (node (ref "R90") (pin "1") (pinfunction "T1_1") (pintype "passive"))
      (node (ref "R91") (pin "1") (pinfunction "T1_1") (pintype "passive"))
    )
    (net (code "17") (name "Net-(C30-T2)") (class "Default")
      (node (ref "C30") (pin "2") (pinfunction "T2_2") (pintype "passive"))
      (node (ref "J15") (pin "6") (pinfunction "6_6") (pintype "passive"))
      (node (ref "R48") (pin "2") (pinfunction "T2_2") (pintype "passive"))
      (node (ref "R92") (pin "2") (pinfunction "T2_2") (pintype "passive"))
      (node (ref "R93") (pin "2") (pinfunction "T2_2") (pintype "passive"))
    )
    (net (code "18") (name "Net-(C75-T1)") (class "Default")
      (node (ref "C75") (pin "1") (pinfunction "T1_1") (pintype "passive"))
      (node (ref "R35") (pin "1") (pinfunction "T1_1") (pintype "passive"))
      (node (ref "R36") (pin "2") (pinfunction "T2_2") (pintype "passive"))
      (node (ref "U14") (pin "2") (pinfunction "INA-_2") (pintype "passive"))
    )
    (net (code "19") (name "Net-(C75-T2)") (class "Default")
      (node (ref "C75") (pin "2") (pinfunction "T2_2") (pintype "passive"))
      (node (ref "R36") (pin "1") (pinfunction "T1_1") (pintype "passive"))
      (node (ref "R37") (pin "2") (pinfunction "T2_2") (pintype "passive"))
      (node (ref "U14") (pin "1") (pinfunction "OUTA_1") (pintype "passive"))
    )
    (net (code "20") (name "Net-(C76-T1)") (class "Default")
      (node (ref "C76") (pin "1") (pinfunction "T1_1") (pintype "passive"))
      (node (ref "R37") (pin "1") (pinfunction "T1_1") (pintype "passive"))
      (node (ref "R38") (pin "2") (pinfunction "T2_2") (pintype "passive"))
      (node (ref "R40") (pin "2") (pinfunction "T2_2") (pintype "passive"))
    )
    (net (code "21") (name "Net-(C77-T2)") (class "Default")
      (node (ref "C77") (pin "2") (pinfunction "T2_2") (pintype "passive"))
      (node (ref "R38") (pin "1") (pinfunction "T1_1") (pintype "passive"))
      (node (ref "U14") (pin "12") (pinfunction "IND+_12") (pintype "passive"))
    )
    (net (code "22") (name "Net-(C78-T2)") (class "Default")
      (node (ref "C78") (pin "2") (pinfunction "T2_2") (pintype "passive"))
      (node (ref "R39") (pin "1") (pinfunction "T1_1") (pintype "passive"))
      (node (ref "R42") (pin "1") (pinfunction "T1_1") (pintype "passive"))
      (node (ref "U14") (pin "3") (pinfunction "INA+_3") (pintype "passive"))
    )
    (net (code "23") (name "Net-(C83-T1)") (class "Default")
      (node (ref "C83") (pin "1") (pinfunction "T1_1") (pintype "passive"))
      (node (ref "R44") (pin "1") (pinfunction "T1_1") (pintype "passive"))
      (node (ref "R45") (pin "2") (pinfunction "T2_2") (pintype "passive"))
      (node (ref "U14") (pin "6") (pinfunction "INB-_6") (pintype "passive"))
    )
    (net (code "24") (name "Net-(C83-T2)") (class "Default")
      (node (ref "C83") (pin "2") (pinfunction "T2_2") (pintype "passive"))
      (node (ref "R45") (pin "1") (pinfunction "T1_1") (pintype "passive"))
      (node (ref "R46") (pin "2") (pinfunction "T2_2") (pintype "passive"))
      (node (ref "U14") (pin "7") (pinfunction "OUTB_7") (pintype "passive"))
    )
    (net (code "25") (name "Net-(C84-T1)") (class "Default")
      (node (ref "C84") (pin "1") (pinfunction "T1_1") (pintype "passive"))
      (node (ref "R46") (pin "1") (pinfunction "T1_1") (pintype "passive"))
      (node (ref "R47") (pin "2") (pinfunction "T2_2") (pintype "passive"))
      (node (ref "R49") (pin "2") (pinfunction "T2_2") (pintype "passive"))
    )
    (net (code "26") (name "Net-(C86-T2)") (class "Default")
      (node (ref "C86") (pin "2") (pinfunction "T2_2") (pintype "passive"))
      (node (ref "R47") (pin "1") (pinfunction "T1_1") (pintype "passive"))
      (node (ref "U14") (pin "10") (pinfunction "INC+_10") (pintype "passive"))
    )
    (net (code "27") (name "Net-(C88-T2)") (class "Default")
      (node (ref "C88") (pin "2") (pinfunction "T2_2") (pintype "passive"))
      (node (ref "R48") (pin "1") (pinfunction "T1_1") (pintype "passive"))
      (node (ref "R51") (pin "1") (pinfunction "T1_1") (pintype "passive"))
      (node (ref "U14") (pin "5") (pinfunction "INB+_5") (pintype "passive"))
    )
    (net (code "28") (name "Net-(C89-T1)") (class "Default")
      (node (ref "C89") (pin "1") (pinfunction "T1_1") (pintype "passive"))
      (node (ref "R53") (pin "1") (pinfunction "T1_1") (pintype "passive"))
      (node (ref "R54") (pin "2") (pinfunction "T2_2") (pintype "passive"))
      (node (ref "U16") (pin "2") (pinfunction "INA-_2") (pintype "passive"))
    )
    (net (code "29") (name "Net-(C89-T2)") (class "Default")
      (node (ref "C89") (pin "2") (pinfunction "T2_2") (pintype "passive"))
      (node (ref "R54") (pin "1") (pinfunction "T1_1") (pintype "passive"))
      (node (ref "R55") (pin "2") (pinfunction "T2_2") (pintype "passive"))
      (node (ref "U16") (pin "1") (pinfunction "OUTA_1") (pintype "passive"))
    )
    (net (code "30") (name "Net-(C90-T1)") (class "Default")
      (node (ref "C90") (pin "1") (pinfunction "T1_1") (pintype "passive"))
      (node (ref "R55") (pin "1") (pinfunction "T1_1") (pintype "passive"))
      (node (ref "R56") (pin "2") (pinfunction "T2_2") (pintype "passive"))
      (node (ref "R58") (pin "2") (pinfunction "T2_2") (pintype "passive"))
    )
    (net (code "31") (name "Net-(C91-T2)") (class "Default")
      (node (ref "C91") (pin "2") (pinfunction "T2_2") (pintype "passive"))
      (node (ref "R56") (pin "1") (pinfunction "T1_1") (pintype "passive"))
      (node (ref "U16") (pin "12") (pinfunction "IND+_12") (pintype "passive"))
    )
    (net (code "32") (name "Net-(C92-T2)") (class "Default")
      (node (ref "C92") (pin "2") (pinfunction "T2_2") (pintype "passive"))
      (node (ref "R57") (pin "1") (pinfunction "T1_1") (pintype "passive"))
      (node (ref "R60") (pin "1") (pinfunction "T1_1") (pintype "passive"))
      (node (ref "U16") (pin "3") (pinfunction "INA+_3") (pintype "passive"))
    )
    (net (code "33") (name "Net-(C93-T1)") (class "Default")
      (node (ref "C93") (pin "1") (pinfunction "T1_1") (pintype "passive"))
      (node (ref "R62") (pin "1") (pinfunction "T1_1") (pintype "passive"))
      (node (ref "R63") (pin "2") (pinfunction "T2_2") (pintype "passive"))
      (node (ref "U16") (pin "6") (pinfunction "INB-_6") (pintype "passive"))
    )
    (net (code "34") (name "Net-(C93-T2)") (class "Default")
      (node (ref "C93") (pin "2") (pinfunction "T2_2") (pintype "passive"))
      (node (ref "R63") (pin "1") (pinfunction "T1_1") (pintype "passive"))
      (node (ref "R64") (pin "2") (pinfunction "T2_2") (pintype "passive"))
      (node (ref "U16") (pin "7") (pinfunction "OUTB_7") (pintype "passive"))
    )
    (net (code "35") (name "Net-(C94-T1)") (class "Default")
      (node (ref "C94") (pin "1") (pinfunction "T1_1") (pintype "passive"))
      (node (ref "R64") (pin "1") (pinfunction "T1_1") (pintype "passive"))
      (node (ref "R65") (pin "2") (pinfunction "T2_2") (pintype "passive"))
      (node (ref "R67") (pin "2") (pinfunction "T2_2") (pintype "passive"))
    )
    (net (code "36") (name "Net-(C95-T2)") (class "Default")
      (node (ref "C95") (pin "2") (pinfunction "T2_2") (pintype "passive"))
      (node (ref "R65") (pin "1") (pinfunction "T1_1") (pintype "passive"))
      (node (ref "U16") (pin "10") (pinfunction "INC+_10") (pintype "passive"))
    )
    (net (code "37") (name "Net-(C96-T2)") (class "Default")
      (node (ref "C96") (pin "2") (pinfunction "T2_2") (pintype "passive"))
      (node (ref "R66") (pin "1") (pinfunction "T1_1") (pintype "passive"))
      (node (ref "R69") (pin "1") (pinfunction "T1_1") (pintype "passive"))
      (node (ref "U16") (pin "5") (pinfunction "INB+_5") (pintype "passive"))
    )
    (net (code "38") (name "Net-(R41-T2)") (class "Default")
      (node (ref "R41") (pin "2") (pinfunction "T2_2") (pintype "passive"))
      (node (ref "R43") (pin "2") (pinfunction "T2_2") (pintype "passive"))
      (node (ref "U14") (pin "13") (pinfunction "IND-_13") (pintype "passive"))
    )
    (net (code "39") (name "Net-(R50-T2)") (class "Default")
      (node (ref "R50") (pin "2") (pinfunction "T2_2") (pintype "passive"))
      (node (ref "R52") (pin "2") (pinfunction "T2_2") (pintype "passive"))
      (node (ref "U14") (pin "9") (pinfunction "INC-_9") (pintype "passive"))
    )
    (net (code "40") (name "Net-(R53-T2)") (class "Default")
      (node (ref "J16") (pin "2") (pinfunction "2_2") (pintype "passive"))
      (node (ref "R53") (pin "2") (pinfunction "T2_2") (pintype "passive"))
    )
    (net (code "41") (name "Net-(R57-T2)") (class "Default")
      (node (ref "J16") (pin "6") (pinfunction "6_6") (pintype "passive"))
      (node (ref "R57") (pin "2") (pinfunction "T2_2") (pintype "passive"))
    )
    (net (code "42") (name "Net-(R59-T2)") (class "Default")
      (node (ref "R59") (pin "2") (pinfunction "T2_2") (pintype "passive"))
      (node (ref "R61") (pin "2") (pinfunction "T2_2") (pintype "passive"))
      (node (ref "U16") (pin "13") (pinfunction "IND-_13") (pintype "passive"))
    )
    (net (code "43") (name "Net-(R68-T2)") (class "Default")
      (node (ref "R68") (pin "2") (pinfunction "T2_2") (pintype "passive"))
      (node (ref "R70") (pin "2") (pinfunction "T2_2") (pintype "passive"))
      (node (ref "U16") (pin "9") (pinfunction "INC-_9") (pintype "passive"))
    )
  )
)
